# tiny-dcdc-2_0.net
KiCad netlist of a schematic drawn in EAGLE
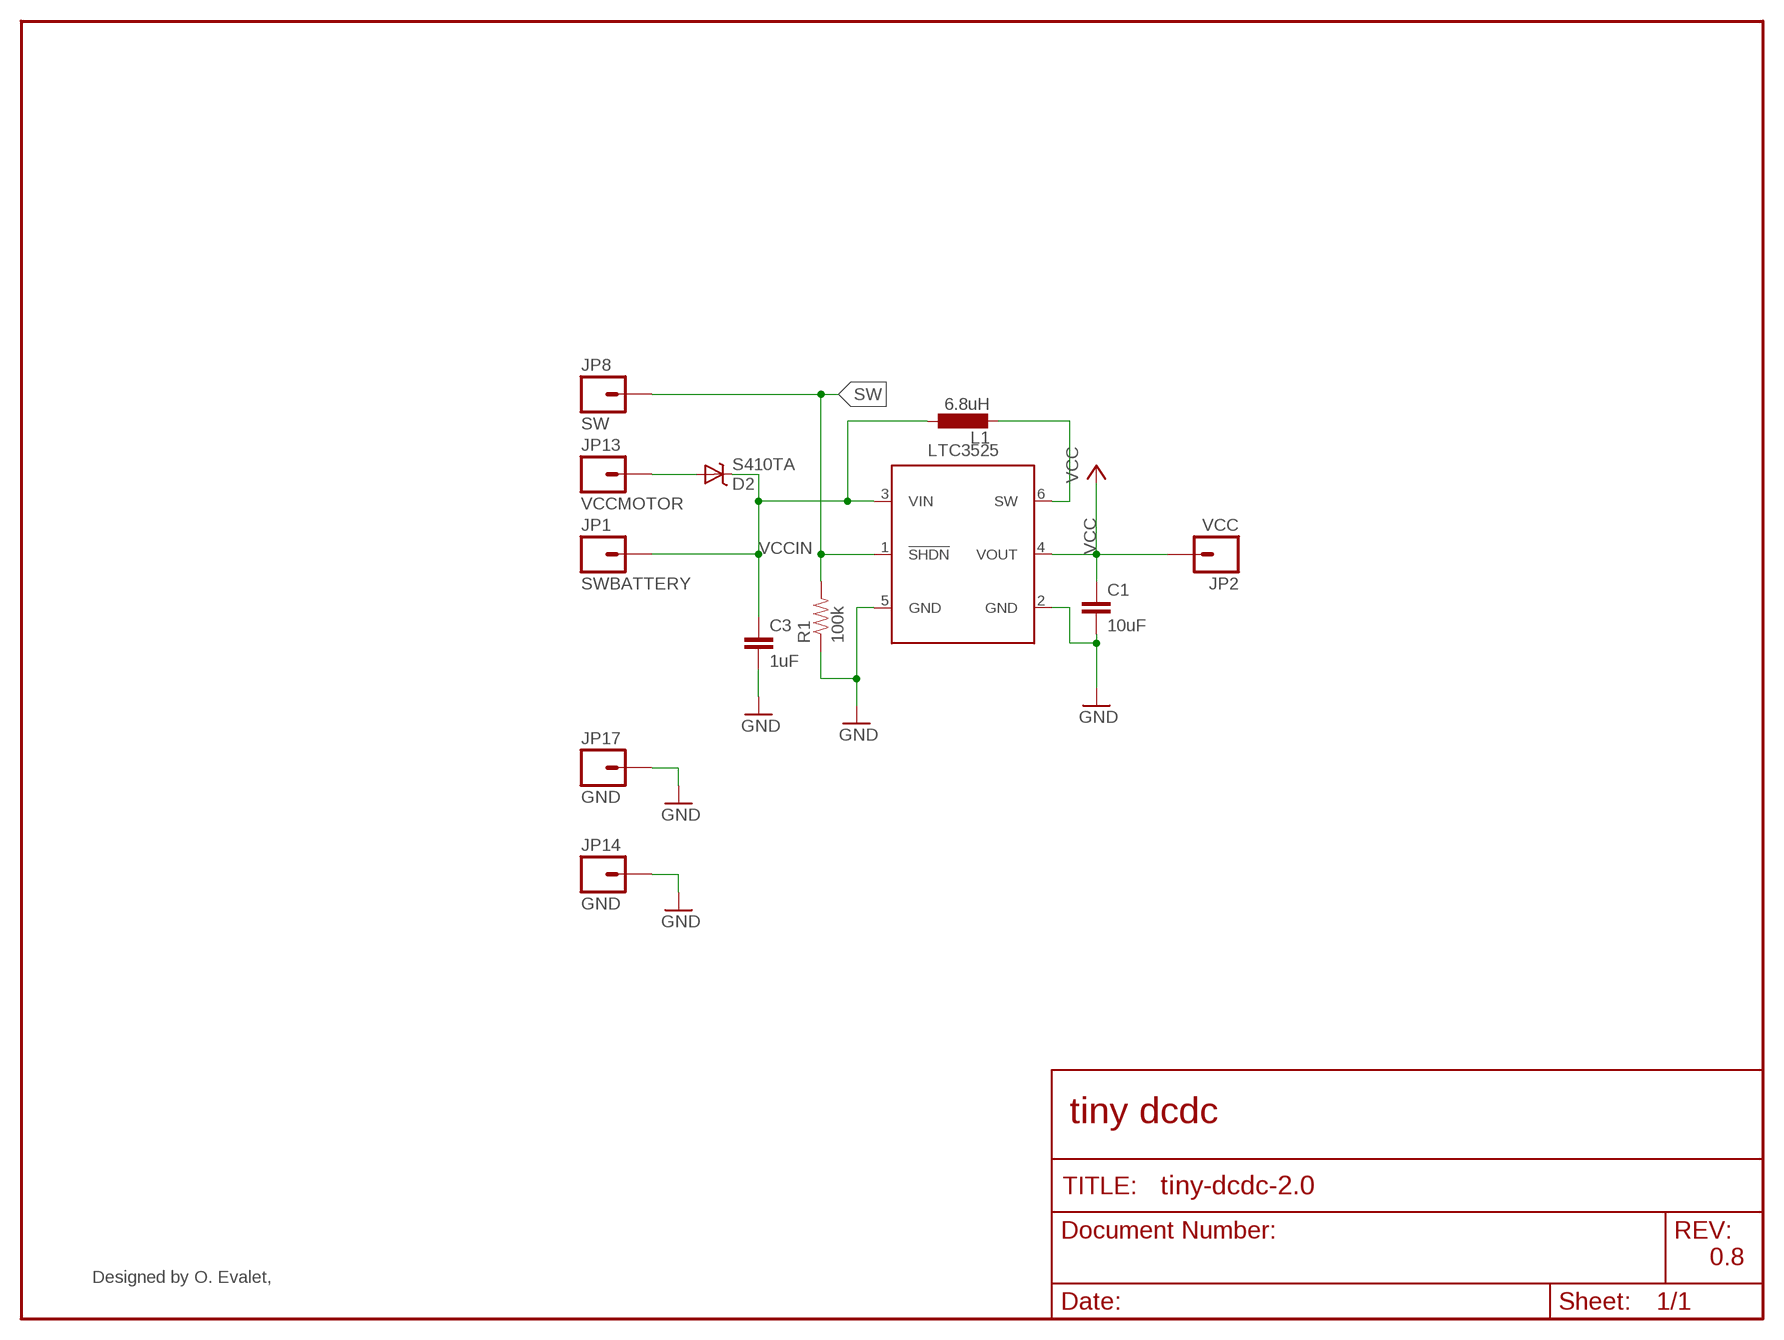
[diagram p0: schematic, sheet 1]

(export (version "E")
  (design (tool "Eeschema 10.0.6"))
  (components
    (comp (ref "C1")
      (value "10uF")
      (footprint "eagle-import:0805")
      (libsource (lib "eagle-import") (part "CAP0805"))
    )
    (comp (ref "C3")
      (value "1uF")
      (footprint "eagle-import:0805")
      (libsource (lib "eagle-import") (part "CAP0805"))
    )
    (comp (ref "D2")
      (value "S410TA")
      (footprint "eagle-import:SOD-323")
      (libsource (lib "eagle-import") (part "DIODE-SCHOTTKYSOD323"))
    )
    (comp (ref "JP1")
      (value "SWBATTERY")
      (footprint "eagle-import:URWERK1X01")
      (libsource (lib "eagle-import") (part "M01URWERK-ROUND"))
    )
    (comp (ref "JP2")
      (value "VCC")
      (footprint "eagle-import:URWERK1X01")
      (libsource (lib "eagle-import") (part "M01URWERK-ROUND"))
    )
    (comp (ref "JP8")
      (value "SW")
      (footprint "eagle-import:URWERK1X01")
      (libsource (lib "eagle-import") (part "M01URWERK-ROUND"))
    )
    (comp (ref "JP13")
      (value "VCCMOTOR")
      (footprint "eagle-import:URWERK1X01")
      (libsource (lib "eagle-import") (part "M01URWERK-ROUND"))
    )
    (comp (ref "JP14")
      (value "GND")
      (footprint "eagle-import:URWERK1X01")
      (libsource (lib "eagle-import") (part "M01URWERK-ROUND"))
    )
    (comp (ref "JP17")
      (value "GND")
      (footprint "eagle-import:URWERK1X01")
      (libsource (lib "eagle-import") (part "M01URWERK-ROUND"))
    )
    (comp (ref "L1")
      (value "6.8uH")
      (footprint "eagle-import:L2012C")
      (libsource (lib "eagle-import") (part "L-EUL2012C"))
    )
    (comp (ref "R1")
      (value "100k")
      (footprint "eagle-import:0805")
      (libsource (lib "eagle-import") (part "RESISTOR0805-RES"))
    )
    (comp (ref "U$3")
      (value "LTC3525")
      (footprint "eagle-import:SC70-6L")
      (libsource (lib "eagle-import") (part "LTC3525"))
    )
  )
  (nets
    (net (code "1") (name "/VCCIN") (class "Default")
      (node (ref "C3") (pin "1") (pinfunction "1_1") (pintype "passive"))
      (node (ref "D2") (pin "1") (pinfunction "C_1") (pintype "passive"))
      (node (ref "JP1") (pin "1") (pinfunction "1_1") (pintype "passive"))
      (node (ref "L1") (pin "1") (pinfunction "1_1") (pintype "passive"))
      (node (ref "U$3") (pin "3") (pinfunction "VIN_3") (pintype "input"))
    )
    (net (code "2") (name "GND") (class "Default")
      (node (ref "C1") (pin "2") (pinfunction "2_2") (pintype "passive"))
      (node (ref "C3") (pin "2") (pinfunction "2_2") (pintype "passive"))
      (node (ref "JP14") (pin "1") (pinfunction "1_1") (pintype "passive"))
      (node (ref "JP17") (pin "1") (pinfunction "1_1") (pintype "passive"))
      (node (ref "R1") (pin "1") (pinfunction "1_1") (pintype "passive"))
      (node (ref "U$3") (pin "2") (pinfunction "GND_2") (pintype "power_in"))
      (node (ref "U$3") (pin "5") (pinfunction "GND_5") (pintype "input"))
    )
    (net (code "3") (name "Net-(D2-A)") (class "Default")
      (node (ref "D2") (pin "2") (pinfunction "A_2") (pintype "passive"))
      (node (ref "JP13") (pin "1") (pinfunction "1_1") (pintype "passive"))
    )
    (net (code "4") (name "Net-(U$3-SW)") (class "Default")
      (node (ref "L1") (pin "2") (pinfunction "2_2") (pintype "passive"))
      (node (ref "U$3") (pin "6") (pinfunction "SW_6") (pintype "passive"))
    )
    (net (code "5") (name "SW") (class "Default")
      (node (ref "JP8") (pin "1") (pinfunction "1_1") (pintype "passive"))
      (node (ref "R1") (pin "2") (pinfunction "2_2") (pintype "passive"))
      (node (ref "U$3") (pin "1") (pinfunction "~{SHDN}_1") (pintype "passive"))
    )
    (net (code "6") (name "VCC") (class "Default")
      (node (ref "C1") (pin "1") (pinfunction "1_1") (pintype "passive"))
      (node (ref "JP2") (pin "1") (pinfunction "1_1") (pintype "passive"))
      (node (ref "U$3") (pin "4") (pinfunction "VOUT_4") (pintype "passive"))
    )
  )
)
